# 1-Schematic_PCIe_riser_to_internal_USB3.net
KiCad netlist of a schematic drawn in EasyEDA
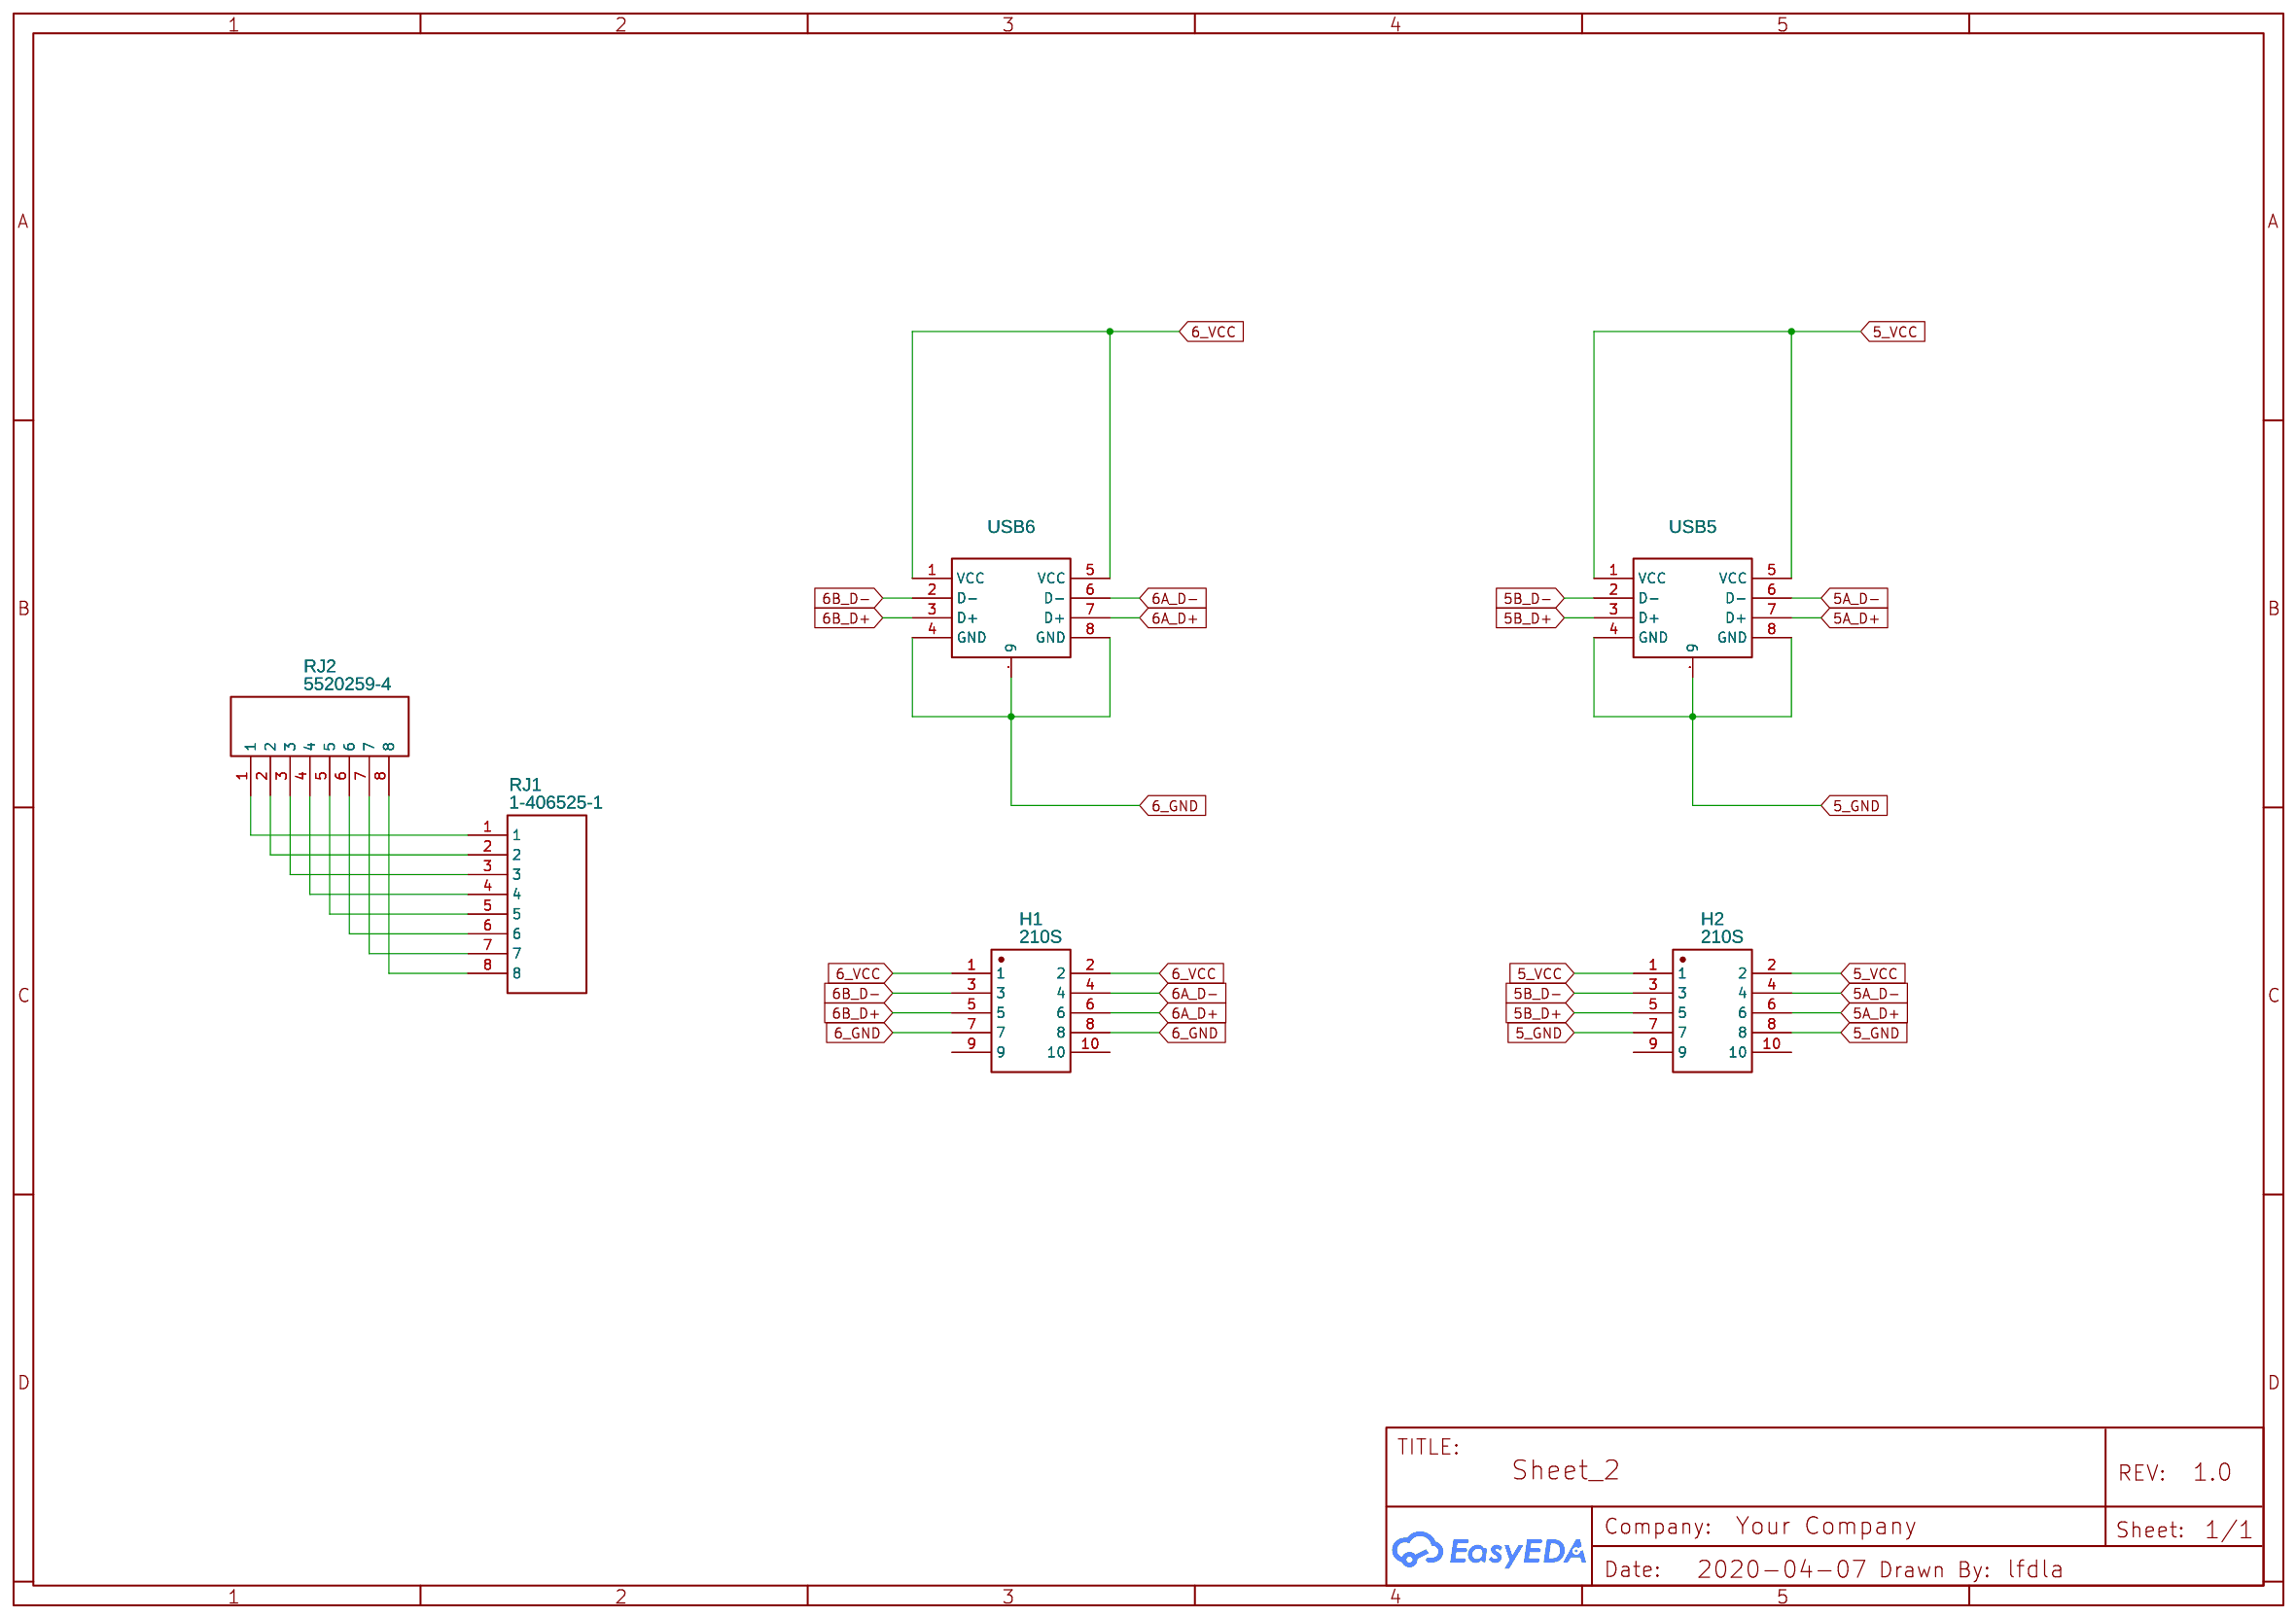
[diagram p0: Sheet_2]
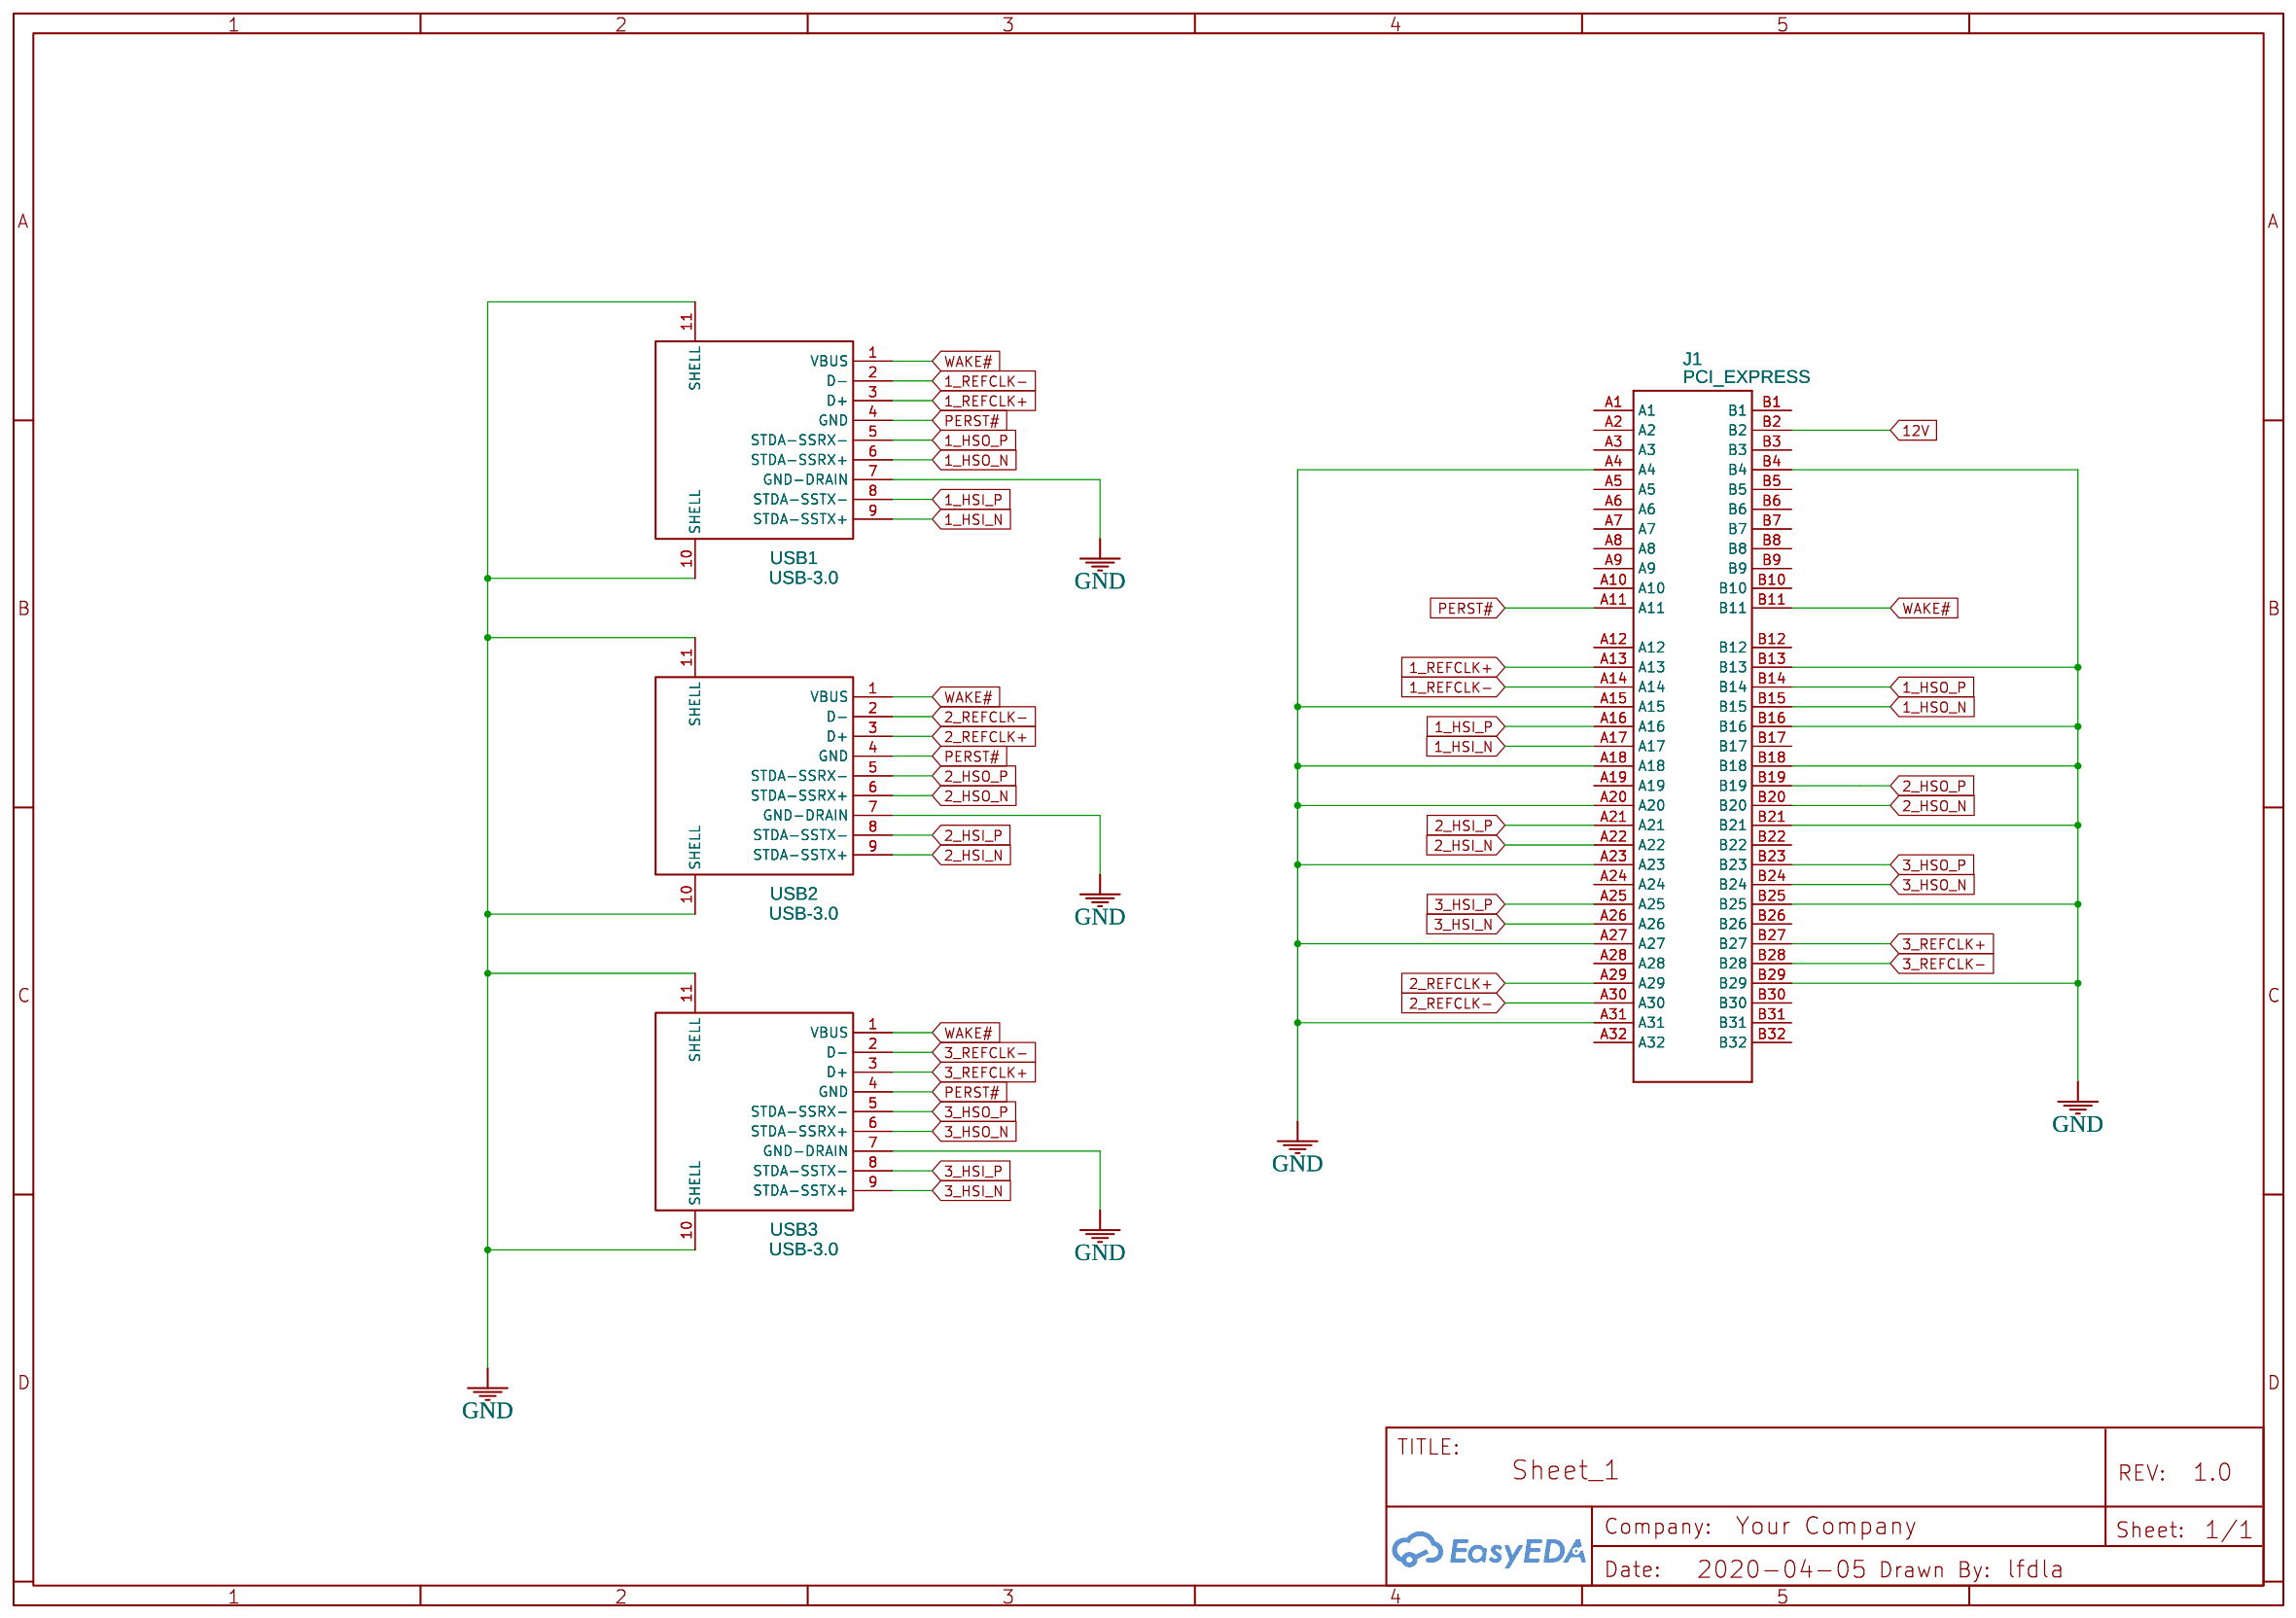
[diagram p1: Sheet_1]

(export (version "E")
  (design (tool "Eeschema 10.0.6"))
  (components
    (comp (ref "H1")
      (value "210S")
      (fields
        (field (name "BOM_Manufacturer Part") "210S-2*5P L=11.6MMGold-plated black")
        (field (name "BOM_Supplier Part") "C124387")
      )
      (libsource (lib "") (part "210S-2*5P L=11.6MMGold-plated black"))
    )
    (comp (ref "H2")
      (value "210S")
      (fields
        (field (name "BOM_Manufacturer Part") "210S-2*5P L=11.6MMGold-plated black")
        (field (name "BOM_Supplier Part") "C124387")
      )
      (libsource (lib "") (part "210S-2*5P L=11.6MMGold-plated black"))
    )
    (comp (ref "RJ1")
      (value "1-406525-1")
      (fields (field (name "BOM_Supplier Part") "C125066"))
      (libsource (lib "") (part "1-406525-1"))
    )
    (comp (ref "RJ2")
      (value "5520259-4")
      (fields (field (name "BOM_Supplier Part") "C86491"))
      (libsource (lib "") (part "5520259-4"))
    )
    (comp (ref "USB5")
      (value "Double layer DIP 90° white")
      (fields (field (name "BOM_Supplier Part") "C2341"))
      (libsource (lib "") (part "Double layer DIP 90° white"))
    )
    (comp (ref "USB6")
      (value "Double layer DIP 90° white")
      (fields (field (name "BOM_Supplier Part") "C2341"))
      (libsource (lib "") (part "Double layer DIP 90° white"))
    )
    (comp (ref "J1")
      (value "PCI_EXPRESS")
      (fields
        (field (name "BOM_Manufacturer Part") "PCI_EXPRESS_PCB")
        (field (name "BOM_Supplier Part") "undefined")
      )
      (libsource (lib "") (part "PCI_EXPRESS_32PIN_MALE_PCB"))
    )
    (comp (ref "USB1")
      (value "USB-3.0")
      (fields
        (field (name "BOM_Manufacturer Part") "USB-3.0-AF-90-16.5X12.5-H6.95")
        (field (name "BOM_Supplier Part") "C69073")
      )
      (libsource (lib "") (part "USB-3.0-AF-90-16.5X12.5-H6.95"))
    )
    (comp (ref "USB2")
      (value "USB-3.0")
      (fields
        (field (name "BOM_Manufacturer Part") "USB-3.0-AF-90-16.5X12.5-H6.95")
        (field (name "BOM_Supplier Part") "C69073")
      )
      (libsource (lib "") (part "USB-3.0-AF-90-16.5X12.5-H6.95"))
    )
    (comp (ref "USB3")
      (value "USB-3.0")
      (fields
        (field (name "BOM_Manufacturer Part") "USB-3.0-AF-90-16.5X12.5-H6.95")
        (field (name "BOM_Supplier Part") "C69073")
      )
      (libsource (lib "") (part "USB-3.0-AF-90-16.5X12.5-H6.95"))
    )
  )
  (nets
    (net (code "1") (name "1_HSI_N") (class "Default")
      (node (ref "J1") (pin "A17") (pinfunction "A17_A17") (pintype "unspecified"))
      (node (ref "USB1") (pin "9") (pinfunction "STDA-SSTX+_9") (pintype "unspecified"))
    )
    (net (code "2") (name "1_HSI_P") (class "Default")
      (node (ref "J1") (pin "A16") (pinfunction "A16_A16") (pintype "unspecified"))
      (node (ref "USB1") (pin "8") (pinfunction "STDA-SSTX-_8") (pintype "unspecified"))
    )
    (net (code "3") (name "1_HSO_N") (class "Default")
      (node (ref "J1") (pin "B15") (pinfunction "B15_B15") (pintype "unspecified"))
      (node (ref "USB1") (pin "6") (pinfunction "STDA-SSRX+_6") (pintype "unspecified"))
    )
    (net (code "4") (name "1_HSO_P") (class "Default")
      (node (ref "J1") (pin "B14") (pinfunction "B14_B14") (pintype "unspecified"))
      (node (ref "USB1") (pin "5") (pinfunction "STDA-SSRX-_5") (pintype "unspecified"))
    )
    (net (code "5") (name "1_REFCLK+") (class "Default")
      (node (ref "J1") (pin "A13") (pinfunction "A13_A13") (pintype "unspecified"))
      (node (ref "USB1") (pin "3") (pinfunction "D+_3") (pintype "unspecified"))
    )
    (net (code "6") (name "1_REFCLK-") (class "Default")
      (node (ref "J1") (pin "A14") (pinfunction "A14_A14") (pintype "unspecified"))
      (node (ref "USB1") (pin "2") (pinfunction "D-_2") (pintype "unspecified"))
    )
    (net (code "7") (name "2_HSI_N") (class "Default")
      (node (ref "J1") (pin "A22") (pinfunction "A22_A22") (pintype "unspecified"))
      (node (ref "USB2") (pin "9") (pinfunction "STDA-SSTX+_9") (pintype "unspecified"))
    )
    (net (code "8") (name "2_HSI_P") (class "Default")
      (node (ref "J1") (pin "A21") (pinfunction "A21_A21") (pintype "unspecified"))
      (node (ref "USB2") (pin "8") (pinfunction "STDA-SSTX-_8") (pintype "unspecified"))
    )
    (net (code "9") (name "2_HSO_N") (class "Default")
      (node (ref "J1") (pin "B20") (pinfunction "B20_B20") (pintype "unspecified"))
      (node (ref "USB2") (pin "6") (pinfunction "STDA-SSRX+_6") (pintype "unspecified"))
    )
    (net (code "10") (name "2_HSO_P") (class "Default")
      (node (ref "J1") (pin "B19") (pinfunction "B19_B19") (pintype "unspecified"))
      (node (ref "USB2") (pin "5") (pinfunction "STDA-SSRX-_5") (pintype "unspecified"))
    )
    (net (code "11") (name "2_REFCLK+") (class "Default")
      (node (ref "J1") (pin "A29") (pinfunction "A29_A29") (pintype "unspecified"))
      (node (ref "USB2") (pin "3") (pinfunction "D+_3") (pintype "unspecified"))
    )
    (net (code "12") (name "2_REFCLK-") (class "Default")
      (node (ref "J1") (pin "A30") (pinfunction "A30_A30") (pintype "unspecified"))
      (node (ref "USB2") (pin "2") (pinfunction "D-_2") (pintype "unspecified"))
    )
    (net (code "13") (name "3_HSI_N") (class "Default")
      (node (ref "J1") (pin "A26") (pinfunction "A26_A26") (pintype "unspecified"))
      (node (ref "USB3") (pin "9") (pinfunction "STDA-SSTX+_9") (pintype "unspecified"))
    )
    (net (code "14") (name "3_HSI_P") (class "Default")
      (node (ref "J1") (pin "A25") (pinfunction "A25_A25") (pintype "unspecified"))
      (node (ref "USB3") (pin "8") (pinfunction "STDA-SSTX-_8") (pintype "unspecified"))
    )
    (net (code "15") (name "3_HSO_N") (class "Default")
      (node (ref "J1") (pin "B24") (pinfunction "B24_B24") (pintype "unspecified"))
      (node (ref "USB3") (pin "6") (pinfunction "STDA-SSRX+_6") (pintype "unspecified"))
    )
    (net (code "16") (name "3_HSO_P") (class "Default")
      (node (ref "J1") (pin "B23") (pinfunction "B23_B23") (pintype "unspecified"))
      (node (ref "USB3") (pin "5") (pinfunction "STDA-SSRX-_5") (pintype "unspecified"))
    )
    (net (code "17") (name "3_REFCLK+") (class "Default")
      (node (ref "J1") (pin "B27") (pinfunction "B27_B27") (pintype "unspecified"))
      (node (ref "USB3") (pin "3") (pinfunction "D+_3") (pintype "unspecified"))
    )
    (net (code "18") (name "3_REFCLK-") (class "Default")
      (node (ref "J1") (pin "B28") (pinfunction "B28_B28") (pintype "unspecified"))
      (node (ref "USB3") (pin "2") (pinfunction "D-_2") (pintype "unspecified"))
    )
    (net (code "19") (name "5A_D+") (class "Default")
      (node (ref "H2") (pin "6") (pinfunction "6_6") (pintype "unspecified"))
      (node (ref "USB5") (pin "7") (pinfunction "D+_7") (pintype "unspecified"))
    )
    (net (code "20") (name "5A_D-") (class "Default")
      (node (ref "H2") (pin "4") (pinfunction "4_4") (pintype "unspecified"))
      (node (ref "USB5") (pin "6") (pinfunction "D-_6") (pintype "unspecified"))
    )
    (net (code "21") (name "5B_D+") (class "Default")
      (node (ref "H2") (pin "5") (pinfunction "5_5") (pintype "unspecified"))
      (node (ref "USB5") (pin "3") (pinfunction "D+_3") (pintype "unspecified"))
    )
    (net (code "22") (name "5B_D-") (class "Default")
      (node (ref "H2") (pin "3") (pinfunction "3_3") (pintype "unspecified"))
      (node (ref "USB5") (pin "2") (pinfunction "D-_2") (pintype "unspecified"))
    )
    (net (code "23") (name "5_GND") (class "Default")
      (node (ref "H2") (pin "7") (pinfunction "7_7") (pintype "unspecified"))
      (node (ref "H2") (pin "8") (pinfunction "8_8") (pintype "unspecified"))
      (node (ref "USB5") (pin "4") (pinfunction "GND_4") (pintype "unspecified"))
      (node (ref "USB5") (pin "8") (pinfunction "GND_8") (pintype "unspecified"))
      (node (ref "USB5") (pin "9") (pinfunction "9_9") (pintype "unspecified"))
    )
    (net (code "24") (name "5_VCC") (class "Default")
      (node (ref "H2") (pin "1") (pinfunction "1_1") (pintype "unspecified"))
      (node (ref "H2") (pin "2") (pinfunction "2_2") (pintype "unspecified"))
      (node (ref "USB5") (pin "1") (pinfunction "VCC_1") (pintype "unspecified"))
      (node (ref "USB5") (pin "5") (pinfunction "VCC_5") (pintype "unspecified"))
    )
    (net (code "25") (name "6A_D+") (class "Default")
      (node (ref "H1") (pin "6") (pinfunction "6_6") (pintype "unspecified"))
      (node (ref "USB6") (pin "7") (pinfunction "D+_7") (pintype "unspecified"))
    )
    (net (code "26") (name "6A_D-") (class "Default")
      (node (ref "H1") (pin "4") (pinfunction "4_4") (pintype "unspecified"))
      (node (ref "USB6") (pin "6") (pinfunction "D-_6") (pintype "unspecified"))
    )
    (net (code "27") (name "6B_D+") (class "Default")
      (node (ref "H1") (pin "5") (pinfunction "5_5") (pintype "unspecified"))
      (node (ref "USB6") (pin "3") (pinfunction "D+_3") (pintype "unspecified"))
    )
    (net (code "28") (name "6B_D-") (class "Default")
      (node (ref "H1") (pin "3") (pinfunction "3_3") (pintype "unspecified"))
      (node (ref "USB6") (pin "2") (pinfunction "D-_2") (pintype "unspecified"))
    )
    (net (code "29") (name "6_GND") (class "Default")
      (node (ref "H1") (pin "7") (pinfunction "7_7") (pintype "unspecified"))
      (node (ref "H1") (pin "8") (pinfunction "8_8") (pintype "unspecified"))
      (node (ref "USB6") (pin "4") (pinfunction "GND_4") (pintype "unspecified"))
      (node (ref "USB6") (pin "8") (pinfunction "GND_8") (pintype "unspecified"))
      (node (ref "USB6") (pin "9") (pinfunction "9_9") (pintype "unspecified"))
    )
    (net (code "30") (name "6_VCC") (class "Default")
      (node (ref "H1") (pin "1") (pinfunction "1_1") (pintype "unspecified"))
      (node (ref "H1") (pin "2") (pinfunction "2_2") (pintype "unspecified"))
      (node (ref "USB6") (pin "1") (pinfunction "VCC_1") (pintype "unspecified"))
      (node (ref "USB6") (pin "5") (pinfunction "VCC_5") (pintype "unspecified"))
    )
    (net (code "31") (name "12V") (class "Default")
      (node (ref "J1") (pin "B2") (pinfunction "B2_B2") (pintype "unspecified"))
    )
    (net (code "32") (name "GND") (class "Default")
      (node (ref "J1") (pin "A15") (pinfunction "A15_A15") (pintype "unspecified"))
      (node (ref "J1") (pin "A18") (pinfunction "A18_A18") (pintype "unspecified"))
      (node (ref "J1") (pin "A20") (pinfunction "A20_A20") (pintype "unspecified"))
      (node (ref "J1") (pin "A23") (pinfunction "A23_A23") (pintype "unspecified"))
      (node (ref "J1") (pin "A27") (pinfunction "A27_A27") (pintype "unspecified"))
      (node (ref "J1") (pin "A31") (pinfunction "A31_A31") (pintype "unspecified"))
      (node (ref "J1") (pin "A4") (pinfunction "A4_A4") (pintype "unspecified"))
      (node (ref "J1") (pin "B13") (pinfunction "B13_B13") (pintype "unspecified"))
      (node (ref "J1") (pin "B16") (pinfunction "B16_B16") (pintype "unspecified"))
      (node (ref "J1") (pin "B18") (pinfunction "B18_B18") (pintype "unspecified"))
      (node (ref "J1") (pin "B21") (pinfunction "B21_B21") (pintype "unspecified"))
      (node (ref "J1") (pin "B25") (pinfunction "B25_B25") (pintype "unspecified"))
      (node (ref "J1") (pin "B29") (pinfunction "B29_B29") (pintype "unspecified"))
      (node (ref "J1") (pin "B4") (pinfunction "B4_B4") (pintype "unspecified"))
      (node (ref "USB1") (pin "10") (pinfunction "SHELL_10") (pintype "unspecified"))
      (node (ref "USB1") (pin "11") (pinfunction "SHELL_11") (pintype "unspecified"))
      (node (ref "USB1") (pin "7") (pinfunction "GND-DRAIN_7") (pintype "unspecified"))
      (node (ref "USB2") (pin "10") (pinfunction "SHELL_10") (pintype "unspecified"))
      (node (ref "USB2") (pin "11") (pinfunction "SHELL_11") (pintype "unspecified"))
      (node (ref "USB2") (pin "7") (pinfunction "GND-DRAIN_7") (pintype "unspecified"))
      (node (ref "USB3") (pin "10") (pinfunction "SHELL_10") (pintype "unspecified"))
      (node (ref "USB3") (pin "11") (pinfunction "SHELL_11") (pintype "unspecified"))
      (node (ref "USB3") (pin "7") (pinfunction "GND-DRAIN_7") (pintype "unspecified"))
    )
    (net (code "33") (name "Net-(RJ1-Pad1)") (class "Default")
      (node (ref "RJ1") (pin "1") (pinfunction "1_1") (pintype "unspecified"))
      (node (ref "RJ2") (pin "1") (pinfunction "1_1") (pintype "unspecified"))
    )
    (net (code "34") (name "Net-(RJ1-Pad2)") (class "Default")
      (node (ref "RJ1") (pin "2") (pinfunction "2_2") (pintype "unspecified"))
      (node (ref "RJ2") (pin "2") (pinfunction "2_2") (pintype "unspecified"))
    )
    (net (code "35") (name "Net-(RJ1-Pad3)") (class "Default")
      (node (ref "RJ1") (pin "3") (pinfunction "3_3") (pintype "unspecified"))
      (node (ref "RJ2") (pin "3") (pinfunction "3_3") (pintype "unspecified"))
    )
    (net (code "36") (name "Net-(RJ1-Pad4)") (class "Default")
      (node (ref "RJ1") (pin "4") (pinfunction "4_4") (pintype "unspecified"))
      (node (ref "RJ2") (pin "4") (pinfunction "4_4") (pintype "unspecified"))
    )
    (net (code "37") (name "Net-(RJ1-Pad5)") (class "Default")
      (node (ref "RJ1") (pin "5") (pinfunction "5_5") (pintype "unspecified"))
      (node (ref "RJ2") (pin "5") (pinfunction "5_5") (pintype "unspecified"))
    )
    (net (code "38") (name "Net-(RJ1-Pad6)") (class "Default")
      (node (ref "RJ1") (pin "6") (pinfunction "6_6") (pintype "unspecified"))
      (node (ref "RJ2") (pin "6") (pinfunction "6_6") (pintype "unspecified"))
    )
    (net (code "39") (name "Net-(RJ1-Pad7)") (class "Default")
      (node (ref "RJ1") (pin "7") (pinfunction "7_7") (pintype "unspecified"))
      (node (ref "RJ2") (pin "7") (pinfunction "7_7") (pintype "unspecified"))
    )
    (net (code "40") (name "Net-(RJ1-Pad8)") (class "Default")
      (node (ref "RJ1") (pin "8") (pinfunction "8_8") (pintype "unspecified"))
      (node (ref "RJ2") (pin "8") (pinfunction "8_8") (pintype "unspecified"))
    )
    (net (code "41") (name "PERST#") (class "Default")
      (node (ref "J1") (pin "A11") (pinfunction "A11_A11") (pintype "unspecified"))
      (node (ref "USB1") (pin "4") (pinfunction "GND_4") (pintype "unspecified"))
      (node (ref "USB2") (pin "4") (pinfunction "GND_4") (pintype "unspecified"))
      (node (ref "USB3") (pin "4") (pinfunction "GND_4") (pintype "unspecified"))
    )
    (net (code "42") (name "WAKE#") (class "Default")
      (node (ref "J1") (pin "B11") (pinfunction "B11_B11") (pintype "unspecified"))
      (node (ref "USB1") (pin "1") (pinfunction "VBUS_1") (pintype "unspecified"))
      (node (ref "USB2") (pin "1") (pinfunction "VBUS_1") (pintype "unspecified"))
      (node (ref "USB3") (pin "1") (pinfunction "VBUS_1") (pintype "unspecified"))
    )
    (net (code "43") (name "unconnected-(H1-Pad9)") (class "Default")
      (node (ref "H1") (pin "9") (pinfunction "9_9") (pintype "unspecified"))
    )
    (net (code "44") (name "unconnected-(H1-Pad10)") (class "Default")
      (node (ref "H1") (pin "10") (pinfunction "10_10") (pintype "unspecified"))
    )
    (net (code "45") (name "unconnected-(H2-Pad9)") (class "Default")
      (node (ref "H2") (pin "9") (pinfunction "9_9") (pintype "unspecified"))
    )
    (net (code "46") (name "unconnected-(H2-Pad10)") (class "Default")
      (node (ref "H2") (pin "10") (pinfunction "10_10") (pintype "unspecified"))
    )
    (net (code "47") (name "unconnected-(J1-PadA1)") (class "Default")
      (node (ref "J1") (pin "A1") (pinfunction "A1_A1") (pintype "unspecified"))
    )
    (net (code "48") (name "unconnected-(J1-PadA2)") (class "Default")
      (node (ref "J1") (pin "A2") (pinfunction "A2_A2") (pintype "unspecified"))
    )
    (net (code "49") (name "unconnected-(J1-PadA3)") (class "Default")
      (node (ref "J1") (pin "A3") (pinfunction "A3_A3") (pintype "unspecified"))
    )
    (net (code "50") (name "unconnected-(J1-PadA5)") (class "Default")
      (node (ref "J1") (pin "A5") (pinfunction "A5_A5") (pintype "unspecified"))
    )
    (net (code "51") (name "unconnected-(J1-PadA6)") (class "Default")
      (node (ref "J1") (pin "A6") (pinfunction "A6_A6") (pintype "unspecified"))
    )
    (net (code "52") (name "unconnected-(J1-PadA7)") (class "Default")
      (node (ref "J1") (pin "A7") (pinfunction "A7_A7") (pintype "unspecified"))
    )
    (net (code "53") (name "unconnected-(J1-PadA8)") (class "Default")
      (node (ref "J1") (pin "A8") (pinfunction "A8_A8") (pintype "unspecified"))
    )
    (net (code "54") (name "unconnected-(J1-PadA9)") (class "Default")
      (node (ref "J1") (pin "A9") (pinfunction "A9_A9") (pintype "unspecified"))
    )
    (net (code "55") (name "unconnected-(J1-PadA10)") (class "Default")
      (node (ref "J1") (pin "A10") (pinfunction "A10_A10") (pintype "unspecified"))
    )
    (net (code "56") (name "unconnected-(J1-PadA12)") (class "Default")
      (node (ref "J1") (pin "A12") (pinfunction "A12_A12") (pintype "unspecified"))
    )
    (net (code "57") (name "unconnected-(J1-PadA19)") (class "Default")
      (node (ref "J1") (pin "A19") (pinfunction "A19_A19") (pintype "unspecified"))
    )
    (net (code "58") (name "unconnected-(J1-PadA24)") (class "Default")
      (node (ref "J1") (pin "A24") (pinfunction "A24_A24") (pintype "unspecified"))
    )
    (net (code "59") (name "unconnected-(J1-PadA28)") (class "Default")
      (node (ref "J1") (pin "A28") (pinfunction "A28_A28") (pintype "unspecified"))
    )
    (net (code "60") (name "unconnected-(J1-PadA32)") (class "Default")
      (node (ref "J1") (pin "A32") (pinfunction "A32_A32") (pintype "unspecified"))
    )
    (net (code "61") (name "unconnected-(J1-PadB1)") (class "Default")
      (node (ref "J1") (pin "B1") (pinfunction "B1_B1") (pintype "unspecified"))
    )
    (net (code "62") (name "unconnected-(J1-PadB3)") (class "Default")
      (node (ref "J1") (pin "B3") (pinfunction "B3_B3") (pintype "unspecified"))
    )
    (net (code "63") (name "unconnected-(J1-PadB5)") (class "Default")
      (node (ref "J1") (pin "B5") (pinfunction "B5_B5") (pintype "unspecified"))
    )
    (net (code "64") (name "unconnected-(J1-PadB6)") (class "Default")
      (node (ref "J1") (pin "B6") (pinfunction "B6_B6") (pintype "unspecified"))
    )
    (net (code "65") (name "unconnected-(J1-PadB7)") (class "Default")
      (node (ref "J1") (pin "B7") (pinfunction "B7_B7") (pintype "unspecified"))
    )
    (net (code "66") (name "unconnected-(J1-PadB8)") (class "Default")
      (node (ref "J1") (pin "B8") (pinfunction "B8_B8") (pintype "unspecified"))
    )
    (net (code "67") (name "unconnected-(J1-PadB9)") (class "Default")
      (node (ref "J1") (pin "B9") (pinfunction "B9_B9") (pintype "unspecified"))
    )
    (net (code "68") (name "unconnected-(J1-PadB10)") (class "Default")
      (node (ref "J1") (pin "B10") (pinfunction "B10_B10") (pintype "unspecified"))
    )
    (net (code "69") (name "unconnected-(J1-PadB12)") (class "Default")
      (node (ref "J1") (pin "B12") (pinfunction "B12_B12") (pintype "unspecified"))
    )
    (net (code "70") (name "unconnected-(J1-PadB17)") (class "Default")
      (node (ref "J1") (pin "B17") (pinfunction "B17_B17") (pintype "unspecified"))
    )
    (net (code "71") (name "unconnected-(J1-PadB22)") (class "Default")
      (node (ref "J1") (pin "B22") (pinfunction "B22_B22") (pintype "unspecified"))
    )
    (net (code "72") (name "unconnected-(J1-PadB26)") (class "Default")
      (node (ref "J1") (pin "B26") (pinfunction "B26_B26") (pintype "unspecified"))
    )
    (net (code "73") (name "unconnected-(J1-PadB30)") (class "Default")
      (node (ref "J1") (pin "B30") (pinfunction "B30_B30") (pintype "unspecified"))
    )
    (net (code "74") (name "unconnected-(J1-PadB31)") (class "Default")
      (node (ref "J1") (pin "B31") (pinfunction "B31_B31") (pintype "unspecified"))
    )
    (net (code "75") (name "unconnected-(J1-PadB32)") (class "Default")
      (node (ref "J1") (pin "B32") (pinfunction "B32_B32") (pintype "unspecified"))
    )
  )
)
